# MOD-W_V10.net
KiCad netlist of a schematic drawn in EAGLE
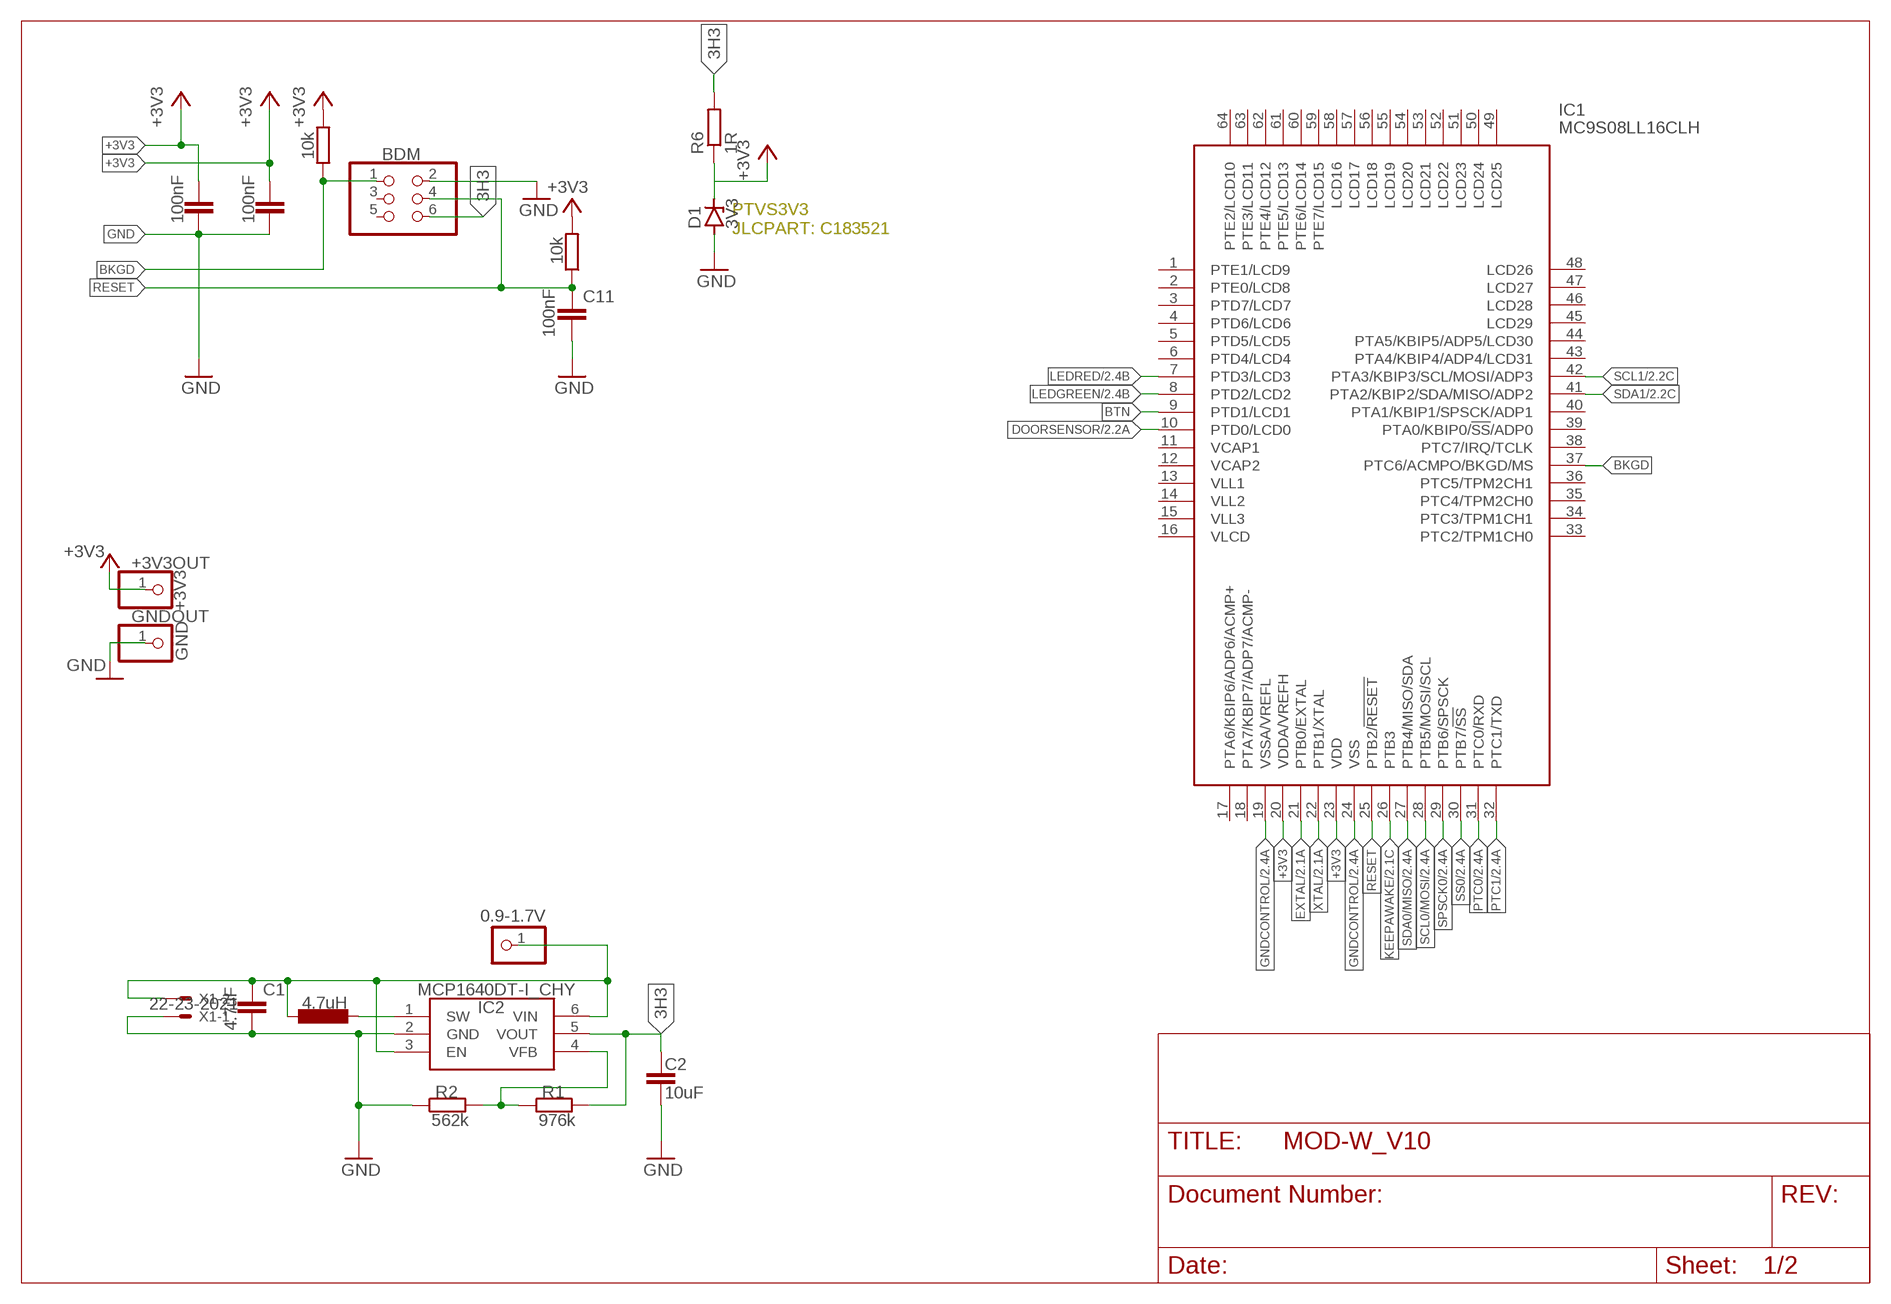
[diagram p0: schematic, sheet 1]
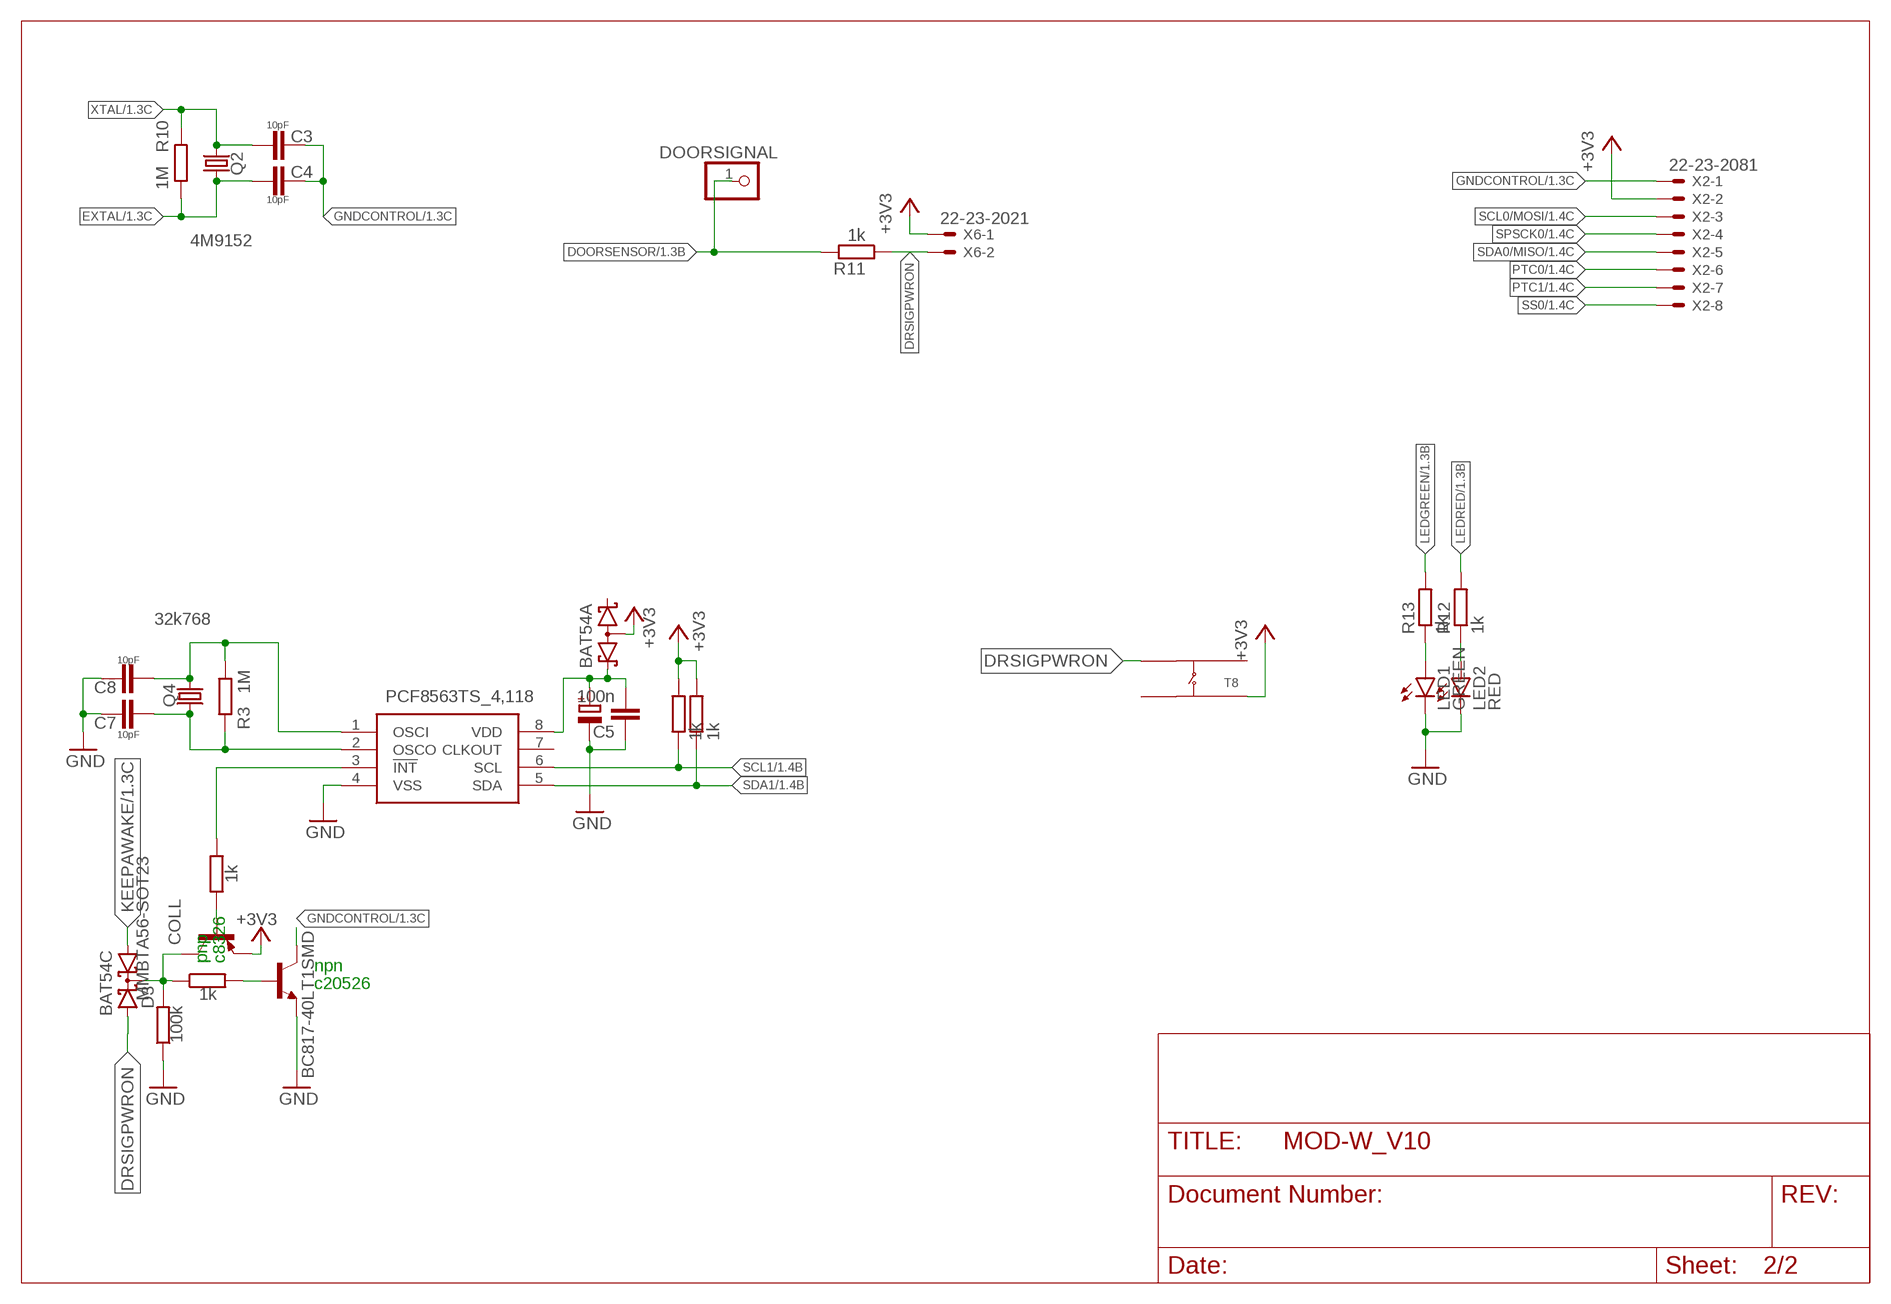
[diagram p1: schematic, sheet 2]

(export (version "E")
  (design (tool "Eeschema 10.0.6"))
  (components
    (comp (ref "C3")
      (value "10pF")
      (footprint "eagle-import:C0805")
      (libsource (lib "eagle-import") (part "C-EUC0805"))
    )
    (comp (ref "C4")
      (value "10pF")
      (footprint "eagle-import:C0805")
      (libsource (lib "eagle-import") (part "C-EUC0805"))
    )
    (comp (ref "C5")
      (value "100n")
      (footprint "eagle-import:C0805")
      (libsource (lib "eagle-import") (part "C-EUC0805"))
    )
    (comp (ref "C6")
      (value "100u")
      (footprint "eagle-import:PANASONIC_E")
      (libsource (lib "eagle-import") (part "CPOL-EUE"))
    )
    (comp (ref "C7")
      (value "10pF")
      (footprint "eagle-import:C0805")
      (libsource (lib "eagle-import") (part "C-EUC0805"))
    )
    (comp (ref "C8")
      (value "10pF")
      (footprint "eagle-import:C0805")
      (libsource (lib "eagle-import") (part "C-EUC0805"))
    )
    (comp (ref "D2")
      (value "BAT54A")
      (footprint "eagle-import:SOT23")
      (libsource (lib "eagle-import") (part "BAT54A"))
    )
    (comp (ref "D3")
      (value "BAT54C")
      (footprint "eagle-import:SOT23")
      (libsource (lib "eagle-import") (part "BAT54C"))
    )
    (comp (ref "DOORSIGNAL")
      (value "PINHD-1X1")
      (footprint "eagle-import:1X01")
      (libsource (lib "eagle-import") (part "PINHD-1X1"))
    )
    (comp (ref "IC3")
      (value "PCF8563TS_4,118")
      (footprint "eagle-import:SOP65P490X110-8N")
      (fields
        (field (name "ARROW_PART_NUMBER") "PCF8563TS/4,118")
        (field (name "MOUSER_PART_NUMBER") "771-PCF8563TS-T")
      )
      (libsource (lib "eagle-import") (part "PCF8563TS_4,118"))
    )
    (comp (ref "LED1")
      (value "GREEN")
      (footprint "eagle-import:CHIP-LED0805")
      (libsource (lib "eagle-import") (part "LEDCHIP-LED0805"))
    )
    (comp (ref "LED2")
      (value "RED")
      (footprint "eagle-import:CHIP-LED0805")
      (libsource (lib "eagle-import") (part "LEDCHIP-LED0805"))
    )
    (comp (ref "Q1")
      (value "MMBTA56-SOT23")
      (footprint "eagle-import:SOT23")
      (libsource (lib "eagle-import") (part "-?SOT23MMBTA56"))
    )
    (comp (ref "Q2")
      (value "4M9152")
      (footprint "eagle-import:HC49UP")
      (libsource (lib "eagle-import") (part "CRYSTALHC49UP"))
    )
    (comp (ref "Q3")
      (value "BC817-40LT1SMD")
      (footprint "eagle-import:SOT23-BEC")
      (libsource (lib "eagle-import") (part "BC817SMD-40LT1"))
    )
    (comp (ref "Q4")
      (value "32k768")
      (footprint "eagle-import:TC38H")
      (libsource (lib "eagle-import") (part "CRYSTALTC38H"))
    )
    (comp (ref "R3")
      (value "1M")
      (footprint "eagle-import:R0805")
      (libsource (lib "eagle-import") (part "R-EU_R0805"))
    )
    (comp (ref "R4")
      (value "1k")
      (footprint "eagle-import:R0805")
      (libsource (lib "eagle-import") (part "R-EU_R0805"))
    )
    (comp (ref "R5")
      (value "1k")
      (footprint "eagle-import:R0805")
      (libsource (lib "eagle-import") (part "R-EU_R0805"))
    )
    (comp (ref "R7")
      (value "1k")
      (footprint "eagle-import:R0805")
      (libsource (lib "eagle-import") (part "R-EU_R0805"))
    )
    (comp (ref "R8")
      (value "1k")
      (footprint "eagle-import:R0805")
      (libsource (lib "eagle-import") (part "R-EU_R0805"))
    )
    (comp (ref "R9")
      (value "100k")
      (footprint "eagle-import:R0805")
      (libsource (lib "eagle-import") (part "R-EU_R0805"))
    )
    (comp (ref "R10")
      (value "1M")
      (footprint "eagle-import:R0805")
      (libsource (lib "eagle-import") (part "R-EU_R0805"))
    )
    (comp (ref "R11")
      (value "1k")
      (footprint "eagle-import:R0805")
      (libsource (lib "eagle-import") (part "R-EU_R0805"))
    )
    (comp (ref "R12")
      (value "1k")
      (footprint "eagle-import:R0805")
      (libsource (lib "eagle-import") (part "R-EU_R0805"))
    )
    (comp (ref "R13")
      (value "1k")
      (footprint "eagle-import:R0805")
      (libsource (lib "eagle-import") (part "R-EU_R0805"))
    )
    (comp (ref "T8")
      (value "TASTERTHT")
      (footprint "eagle-import:TASTE_THT")
      (libsource (lib "eagle-import") (part "TASTERTHT"))
    )
    (comp (ref "X2")
      (value "22-23-2081")
      (footprint "eagle-import:22-23-2081")
      (fields (field (name "MF") "MOLEX"))
      (libsource (lib "eagle-import") (part "22-23-2081"))
    )
    (comp (ref "X6")
      (value "22-23-2021")
      (footprint "eagle-import:22-23-2021")
      (fields (field (name "MF") "MOLEX"))
      (libsource (lib "eagle-import") (part "22-23-2021"))
    )
    (comp (ref "+3V3OUT")
      (value "+3V3")
      (footprint "eagle-import:1X01")
      (libsource (lib "eagle-import") (part "PINHD-1X1"))
    )
    (comp (ref "BAT")
      (value "0.9-1.7V")
      (footprint "eagle-import:1X01")
      (libsource (lib "eagle-import") (part "PINHD-1X1"))
    )
    (comp (ref "BDM")
      (value "PINHD-2X3")
      (footprint "eagle-import:2X03")
      (libsource (lib "eagle-import") (part "PINHD-2X3"))
    )
    (comp (ref "C1")
      (value "4.7uF")
      (footprint "eagle-import:C0805")
      (libsource (lib "eagle-import") (part "C-EUC0805"))
    )
    (comp (ref "C2")
      (value "10uF")
      (footprint "eagle-import:C0805")
      (libsource (lib "eagle-import") (part "C-EUC0805"))
    )
    (comp (ref "C9")
      (value "100nF")
      (footprint "eagle-import:C0805")
      (libsource (lib "eagle-import") (part "C-EUC0805"))
    )
    (comp (ref "C10")
      (value "100nF")
      (footprint "eagle-import:C0805")
      (libsource (lib "eagle-import") (part "C-EUC0805"))
    )
    (comp (ref "C11")
      (value "100nF")
      (footprint "eagle-import:C0805")
      (libsource (lib "eagle-import") (part "C-EUC0805"))
    )
    (comp (ref "D1")
      (value "3V3")
      (footprint "eagle-import:SOD80C")
      (libsource (lib "eagle-import") (part "ZENER-DIODESOD80C"))
    )
    (comp (ref "GNDOUT")
      (value "GND")
      (footprint "eagle-import:1X01")
      (libsource (lib "eagle-import") (part "PINHD-1X1"))
    )
    (comp (ref "IC1")
      (value "MC9S08LL16CLH")
      (footprint "eagle-import:QFP50P1200X1200X160-64N")
      (fields (field (name "MOUSER_PART_NUMBER") "841-MC9S08LL16CLH"))
      (libsource (lib "eagle-import") (part "MC9S08LL16CLH"))
    )
    (comp (ref "IC2")
      (value "MCP1640DT-I_CHY")
      (footprint "eagle-import:SOT95P270X145-6N")
      (fields
        (field (name "ARROW_PART_NUMBER") "MCP1640DT-I/CHY")
        (field (name "MOUSER_PART_NUMBER") "579-MCP1640DT-I/CHY")
      )
      (libsource (lib "eagle-import") (part "MCP1640DT-I_CHY"))
    )
    (comp (ref "L1")
      (value "4.7uH")
      (footprint "eagle-import:L2012C")
      (libsource (lib "eagle-import") (part "L-EUL2012C"))
    )
    (comp (ref "R1")
      (value "976k")
      (footprint "eagle-import:R0805")
      (libsource (lib "eagle-import") (part "R-EU_R0805"))
    )
    (comp (ref "R2")
      (value "562k")
      (footprint "eagle-import:R0805")
      (libsource (lib "eagle-import") (part "R-EU_R0805"))
    )
    (comp (ref "R6")
      (value "1R")
      (footprint "eagle-import:R0805")
      (libsource (lib "eagle-import") (part "R-EU_R0805"))
    )
    (comp (ref "R16")
      (value "10k")
      (footprint "eagle-import:R0805")
      (libsource (lib "eagle-import") (part "R-EU_R0805"))
    )
    (comp (ref "R17")
      (value "10k")
      (footprint "eagle-import:R0805")
      (libsource (lib "eagle-import") (part "R-EU_R0805"))
    )
    (comp (ref "X1")
      (value "22-23-2021")
      (footprint "eagle-import:22-23-2021")
      (fields (field (name "MF") "MOLEX"))
      (libsource (lib "eagle-import") (part "22-23-2021"))
    )
  )
  (nets
    (net (code "1") (name "+3V3") (class "Default")
      (node (ref "+3V3OUT") (pin "1") (pinfunction "1_1") (pintype "passive"))
      (node (ref "C10") (pin "1") (pinfunction "1_1") (pintype "passive"))
      (node (ref "C9") (pin "1") (pinfunction "1_1") (pintype "passive"))
      (node (ref "D1") (pin "C") (pinfunction "C_C") (pintype "passive"))
      (node (ref "D2") (pin "3") (pinfunction "AA_3") (pintype "passive"))
      (node (ref "IC1") (pin "20") (pinfunction "VDDA/VREFH_20") (pintype "bidirectional"))
      (node (ref "IC1") (pin "23") (pinfunction "VDD_23") (pintype "bidirectional"))
      (node (ref "Q1") (pin "2") (pinfunction "E_2") (pintype "passive"))
      (node (ref "R16") (pin "2") (pinfunction "2_2") (pintype "passive"))
      (node (ref "R17") (pin "2") (pinfunction "2_2") (pintype "passive"))
      (node (ref "R4") (pin "2") (pinfunction "2_2") (pintype "passive"))
      (node (ref "R5") (pin "2") (pinfunction "2_2") (pintype "passive"))
      (node (ref "R6") (pin "1") (pinfunction "1_1") (pintype "passive"))
      (node (ref "T8") (pin "A1") (pinfunction "A1_A1") (pintype "bidirectional"))
      (node (ref "X2") (pin "2") (pinfunction "S_2") (pintype "passive"))
      (node (ref "X6") (pin "1") (pinfunction "S_1") (pintype "passive"))
    )
    (net (code "2") (name "3H3") (class "Default")
      (node (ref "BDM") (pin "6") (pinfunction "6_6") (pintype "passive"))
      (node (ref "C2") (pin "1") (pinfunction "1_1") (pintype "passive"))
      (node (ref "IC2") (pin "5") (pinfunction "VOUT_5") (pintype "output"))
      (node (ref "R1") (pin "2") (pinfunction "2_2") (pintype "passive"))
      (node (ref "R6") (pin "2") (pinfunction "2_2") (pintype "passive"))
    )
    (net (code "3") (name "BKGD") (class "Default")
      (node (ref "BDM") (pin "1") (pinfunction "1_1") (pintype "passive"))
      (node (ref "IC1") (pin "37") (pinfunction "PTC6/ACMPO/BKGD/MS_37") (pintype "bidirectional"))
      (node (ref "R16") (pin "1") (pinfunction "1_1") (pintype "passive"))
    )
    (net (code "4") (name "BTN") (class "Default")
      (node (ref "IC1") (pin "9") (pinfunction "PTD1/LCD1_9") (pintype "bidirectional"))
    )
    (net (code "5") (name "COLL") (class "Default")
      (node (ref "D3") (pin "3") (pinfunction "CC_3") (pintype "passive"))
      (node (ref "Q1") (pin "3") (pinfunction "C_3") (pintype "passive"))
      (node (ref "R7") (pin "1") (pinfunction "1_1") (pintype "passive"))
      (node (ref "R9") (pin "2") (pinfunction "2_2") (pintype "passive"))
    )
    (net (code "6") (name "DOORSENSOR") (class "Default")
      (node (ref "DOORSIGNAL") (pin "1") (pinfunction "1_1") (pintype "passive"))
      (node (ref "IC1") (pin "10") (pinfunction "PTD0/LCD0_10") (pintype "bidirectional"))
      (node (ref "R11") (pin "2") (pinfunction "2_2") (pintype "passive"))
    )
    (net (code "7") (name "DRSIGPWRON") (class "Default")
      (node (ref "D3") (pin "2") (pinfunction "A2_2") (pintype "passive"))
      (node (ref "R11") (pin "1") (pinfunction "1_1") (pintype "passive"))
      (node (ref "T8") (pin "B2") (pinfunction "B2_B2") (pintype "bidirectional"))
      (node (ref "X6") (pin "2") (pinfunction "S_2") (pintype "passive"))
    )
    (net (code "8") (name "EXTAL") (class "Default")
      (node (ref "C4") (pin "1") (pinfunction "1_1") (pintype "passive"))
      (node (ref "IC1") (pin "21") (pinfunction "PTB0/EXTAL_21") (pintype "bidirectional"))
      (node (ref "Q2") (pin "1") (pinfunction "1_1") (pintype "passive"))
      (node (ref "R10") (pin "1") (pinfunction "1_1") (pintype "passive"))
    )
    (net (code "9") (name "GND") (class "Default")
      (node (ref "BDM") (pin "2") (pinfunction "2_2") (pintype "passive"))
      (node (ref "C1") (pin "2") (pinfunction "2_2") (pintype "passive"))
      (node (ref "C10") (pin "2") (pinfunction "2_2") (pintype "passive"))
      (node (ref "C11") (pin "2") (pinfunction "2_2") (pintype "passive"))
      (node (ref "C2") (pin "2") (pinfunction "2_2") (pintype "passive"))
      (node (ref "C5") (pin "1") (pinfunction "1_1") (pintype "passive"))
      (node (ref "C6") (pin "-") (pinfunction "-_-") (pintype "passive"))
      (node (ref "C7") (pin "2") (pinfunction "2_2") (pintype "passive"))
      (node (ref "C8") (pin "2") (pinfunction "2_2") (pintype "passive"))
      (node (ref "C9") (pin "2") (pinfunction "2_2") (pintype "passive"))
      (node (ref "D1") (pin "A") (pinfunction "A_A") (pintype "passive"))
      (node (ref "GNDOUT") (pin "1") (pinfunction "1_1") (pintype "passive"))
      (node (ref "IC2") (pin "2") (pinfunction "GND_2") (pintype "power_in"))
      (node (ref "IC3") (pin "4") (pinfunction "VSS_4") (pintype "bidirectional"))
      (node (ref "LED1") (pin "C") (pinfunction "C_C") (pintype "passive"))
      (node (ref "LED2") (pin "C") (pinfunction "C_C") (pintype "passive"))
      (node (ref "Q3") (pin "E") (pinfunction "E_E") (pintype "passive"))
      (node (ref "R2") (pin "1") (pinfunction "1_1") (pintype "passive"))
      (node (ref "R9") (pin "1") (pinfunction "1_1") (pintype "passive"))
      (node (ref "X1") (pin "1") (pinfunction "S_1") (pintype "passive"))
    )
    (net (code "10") (name "GNDCONTROL") (class "Default")
      (node (ref "C3") (pin "2") (pinfunction "2_2") (pintype "passive"))
      (node (ref "C4") (pin "2") (pinfunction "2_2") (pintype "passive"))
      (node (ref "IC1") (pin "19") (pinfunction "VSSA/VREFL_19") (pintype "bidirectional"))
      (node (ref "IC1") (pin "24") (pinfunction "VSS_24") (pintype "bidirectional"))
      (node (ref "Q3") (pin "C") (pinfunction "C_C") (pintype "passive"))
      (node (ref "X2") (pin "1") (pinfunction "S_1") (pintype "passive"))
    )
    (net (code "11") (name "KEEPAWAKE") (class "Default")
      (node (ref "D3") (pin "1") (pinfunction "A1_1") (pintype "passive"))
      (node (ref "IC1") (pin "26") (pinfunction "PTB3_26") (pintype "bidirectional"))
    )
    (net (code "12") (name "LEDGREEN") (class "Default")
      (node (ref "IC1") (pin "8") (pinfunction "PTD2/LCD2_8") (pintype "bidirectional"))
      (node (ref "R13") (pin "2") (pinfunction "2_2") (pintype "passive"))
    )
    (net (code "13") (name "LEDRED") (class "Default")
      (node (ref "IC1") (pin "7") (pinfunction "PTD3/LCD3_7") (pintype "bidirectional"))
      (node (ref "R12") (pin "2") (pinfunction "2_2") (pintype "passive"))
    )
    (net (code "14") (name "Net-(D2-K2)") (class "Default")
      (node (ref "C5") (pin "2") (pinfunction "2_2") (pintype "passive"))
      (node (ref "C6") (pin "+") (pinfunction "+_+") (pintype "passive"))
      (node (ref "D2") (pin "2") (pinfunction "K2_2") (pintype "passive"))
      (node (ref "IC3") (pin "8") (pinfunction "VDD_8") (pintype "bidirectional"))
    )
    (net (code "15") (name "Net-(IC2-EN)") (class "Default")
      (node (ref "BAT") (pin "1") (pinfunction "1_1") (pintype "passive"))
      (node (ref "C1") (pin "1") (pinfunction "1_1") (pintype "passive"))
      (node (ref "IC2") (pin "3") (pinfunction "EN_3") (pintype "power_in"))
      (node (ref "IC2") (pin "6") (pinfunction "VIN_6") (pintype "input"))
      (node (ref "L1") (pin "2") (pinfunction "2_2") (pintype "passive"))
      (node (ref "X1") (pin "2") (pinfunction "S_2") (pintype "passive"))
    )
    (net (code "16") (name "Net-(IC2-SW)") (class "Default")
      (node (ref "IC2") (pin "1") (pinfunction "SW_1") (pintype "input"))
      (node (ref "L1") (pin "1") (pinfunction "1_1") (pintype "passive"))
    )
    (net (code "17") (name "Net-(IC2-VFB)") (class "Default")
      (node (ref "IC2") (pin "4") (pinfunction "VFB_4") (pintype "bidirectional"))
      (node (ref "R1") (pin "1") (pinfunction "1_1") (pintype "passive"))
      (node (ref "R2") (pin "2") (pinfunction "2_2") (pintype "passive"))
    )
    (net (code "18") (name "Net-(IC3-OSCI)") (class "Default")
      (node (ref "C8") (pin "1") (pinfunction "1_1") (pintype "passive"))
      (node (ref "IC3") (pin "1") (pinfunction "OSCI_1") (pintype "bidirectional"))
      (node (ref "Q4") (pin "1") (pinfunction "1_1") (pintype "passive"))
      (node (ref "R3") (pin "1") (pinfunction "1_1") (pintype "passive"))
    )
    (net (code "19") (name "Net-(IC3-OSCO)") (class "Default")
      (node (ref "C7") (pin "1") (pinfunction "1_1") (pintype "passive"))
      (node (ref "IC3") (pin "2") (pinfunction "OSCO_2") (pintype "bidirectional"))
      (node (ref "Q4") (pin "2") (pinfunction "2_2") (pintype "passive"))
      (node (ref "R3") (pin "2") (pinfunction "2_2") (pintype "passive"))
    )
    (net (code "20") (name "Net-(IC3-~{INT})") (class "Default")
      (node (ref "IC3") (pin "3") (pinfunction "~{INT}_3") (pintype "bidirectional"))
      (node (ref "R8") (pin "2") (pinfunction "2_2") (pintype "passive"))
    )
    (net (code "21") (name "Net-(LED1-PadA)") (class "Default")
      (node (ref "LED1") (pin "A") (pinfunction "A_A") (pintype "passive"))
      (node (ref "R13") (pin "1") (pinfunction "1_1") (pintype "passive"))
    )
    (net (code "22") (name "Net-(LED2-PadA)") (class "Default")
      (node (ref "LED2") (pin "A") (pinfunction "A_A") (pintype "passive"))
      (node (ref "R12") (pin "1") (pinfunction "1_1") (pintype "passive"))
    )
    (net (code "23") (name "Net-(Q1-B)") (class "Default")
      (node (ref "Q1") (pin "1") (pinfunction "B_1") (pintype "passive"))
      (node (ref "R8") (pin "1") (pinfunction "1_1") (pintype "passive"))
    )
    (net (code "24") (name "Net-(Q3-PadB)") (class "Default")
      (node (ref "Q3") (pin "B") (pinfunction "B_B") (pintype "passive"))
      (node (ref "R7") (pin "2") (pinfunction "2_2") (pintype "passive"))
    )
    (net (code "25") (name "PTC0") (class "Default")
      (node (ref "IC1") (pin "31") (pinfunction "PTC0/RXD_31") (pintype "bidirectional"))
      (node (ref "X2") (pin "6") (pinfunction "S_6") (pintype "passive"))
    )
    (net (code "26") (name "PTC1") (class "Default")
      (node (ref "IC1") (pin "32") (pinfunction "PTC1/TXD_32") (pintype "bidirectional"))
      (node (ref "X2") (pin "7") (pinfunction "S_7") (pintype "passive"))
    )
    (net (code "27") (name "RESET") (class "Default")
      (node (ref "BDM") (pin "4") (pinfunction "4_4") (pintype "passive"))
      (node (ref "C11") (pin "1") (pinfunction "1_1") (pintype "passive"))
      (node (ref "IC1") (pin "25") (pinfunction "PTB2/~{RESET}_25") (pintype "bidirectional"))
      (node (ref "R17") (pin "1") (pinfunction "1_1") (pintype "passive"))
    )
    (net (code "28") (name "SCL0{slash}MOSI") (class "Default")
      (node (ref "IC1") (pin "28") (pinfunction "PTB5/MOSI/SCL_28") (pintype "bidirectional"))
      (node (ref "X2") (pin "3") (pinfunction "S_3") (pintype "passive"))
    )
    (net (code "29") (name "SCL1") (class "Default")
      (node (ref "IC1") (pin "42") (pinfunction "PTA3/KBIP3/SCL/MOSI/ADP3_42") (pintype "bidirectional"))
      (node (ref "IC3") (pin "6") (pinfunction "SCL_6") (pintype "bidirectional"))
      (node (ref "R4") (pin "1") (pinfunction "1_1") (pintype "passive"))
    )
    (net (code "30") (name "SDA0{slash}MISO") (class "Default")
      (node (ref "IC1") (pin "27") (pinfunction "PTB4/MISO/SDA_27") (pintype "bidirectional"))
      (node (ref "X2") (pin "5") (pinfunction "S_5") (pintype "passive"))
    )
    (net (code "31") (name "SDA1") (class "Default")
      (node (ref "IC1") (pin "41") (pinfunction "PTA2/KBIP2/SDA/MISO/ADP2_41") (pintype "bidirectional"))
      (node (ref "IC3") (pin "5") (pinfunction "SDA_5") (pintype "bidirectional"))
      (node (ref "R5") (pin "1") (pinfunction "1_1") (pintype "passive"))
    )
    (net (code "32") (name "SPSCK0") (class "Default")
      (node (ref "IC1") (pin "29") (pinfunction "PTB6/SPSCK_29") (pintype "bidirectional"))
      (node (ref "X2") (pin "4") (pinfunction "S_4") (pintype "passive"))
    )
    (net (code "33") (name "SS0") (class "Default")
      (node (ref "IC1") (pin "30") (pinfunction "PTB7/~{SS}_30") (pintype "bidirectional"))
      (node (ref "X2") (pin "8") (pinfunction "S_8") (pintype "passive"))
    )
    (net (code "34") (name "XTAL") (class "Default")
      (node (ref "C3") (pin "1") (pinfunction "1_1") (pintype "passive"))
      (node (ref "IC1") (pin "22") (pinfunction "PTB1/XTAL_22") (pintype "bidirectional"))
      (node (ref "Q2") (pin "2") (pinfunction "2_2") (pintype "passive"))
      (node (ref "R10") (pin "2") (pinfunction "2_2") (pintype "passive"))
    )
    (net (code "35") (name "unconnected-(BDM-Pad3)") (class "Default")
      (node (ref "BDM") (pin "3") (pinfunction "3_3") (pintype "passive"))
    )
    (net (code "36") (name "unconnected-(BDM-Pad5)") (class "Default")
      (node (ref "BDM") (pin "5") (pinfunction "5_5") (pintype "passive"))
    )
    (net (code "37") (name "unconnected-(D2-K1-Pad1)") (class "Default")
      (node (ref "D2") (pin "1") (pinfunction "K1_1") (pintype "passive"))
    )
    (net (code "38") (name "unconnected-(IC1-LCD16-Pad58)") (class "Default")
      (node (ref "IC1") (pin "58") (pinfunction "LCD16_58") (pintype "bidirectional"))
    )
    (net (code "39") (name "unconnected-(IC1-LCD17-Pad57)") (class "Default")
      (node (ref "IC1") (pin "57") (pinfunction "LCD17_57") (pintype "bidirectional"))
    )
    (net (code "40") (name "unconnected-(IC1-LCD18-Pad56)") (class "Default")
      (node (ref "IC1") (pin "56") (pinfunction "LCD18_56") (pintype "bidirectional"))
    )
    (net (code "41") (name "unconnected-(IC1-LCD19-Pad55)") (class "Default")
      (node (ref "IC1") (pin "55") (pinfunction "LCD19_55") (pintype "bidirectional"))
    )
    (net (code "42") (name "unconnected-(IC1-LCD20-Pad54)") (class "Default")
      (node (ref "IC1") (pin "54") (pinfunction "LCD20_54") (pintype "bidirectional"))
    )
    (net (code "43") (name "unconnected-(IC1-LCD21-Pad53)") (class "Default")
      (node (ref "IC1") (pin "53") (pinfunction "LCD21_53") (pintype "bidirectional"))
    )
    (net (code "44") (name "unconnected-(IC1-LCD22-Pad52)") (class "Default")
      (node (ref "IC1") (pin "52") (pinfunction "LCD22_52") (pintype "bidirectional"))
    )
    (net (code "45") (name "unconnected-(IC1-LCD23-Pad51)") (class "Default")
      (node (ref "IC1") (pin "51") (pinfunction "LCD23_51") (pintype "bidirectional"))
    )
    (net (code "46") (name "unconnected-(IC1-LCD24-Pad50)") (class "Default")
      (node (ref "IC1") (pin "50") (pinfunction "LCD24_50") (pintype "bidirectional"))
    )
    (net (code "47") (name "unconnected-(IC1-LCD25-Pad49)") (class "Default")
      (node (ref "IC1") (pin "49") (pinfunction "LCD25_49") (pintype "bidirectional"))
    )
    (net (code "48") (name "unconnected-(IC1-LCD26-Pad48)") (class "Default")
      (node (ref "IC1") (pin "48") (pinfunction "LCD26_48") (pintype "bidirectional"))
    )
    (net (code "49") (name "unconnected-(IC1-LCD27-Pad47)") (class "Default")
      (node (ref "IC1") (pin "47") (pinfunction "LCD27_47") (pintype "bidirectional"))
    )
    (net (code "50") (name "unconnected-(IC1-LCD28-Pad46)") (class "Default")
      (node (ref "IC1") (pin "46") (pinfunction "LCD28_46") (pintype "bidirectional"))
    )
    (net (code "51") (name "unconnected-(IC1-LCD29-Pad45)") (class "Default")
      (node (ref "IC1") (pin "45") (pinfunction "LCD29_45") (pintype "bidirectional"))
    )
    (net (code "52") (name "unconnected-(IC1-PTA0{slash}KBIP0{slash}~{SS}{slash}ADP0-Pad39)") (class "Default")
      (node (ref "IC1") (pin "39") (pinfunction "PTA0/KBIP0/~{SS}/ADP0_39") (pintype "bidirectional"))
    )
    (net (code "53") (name "unconnected-(IC1-PTA1{slash}KBIP1{slash}SPSCK{slash}ADP1-Pad40)") (class "Default")
      (node (ref "IC1") (pin "40") (pinfunction "PTA1/KBIP1/SPSCK/ADP1_40") (pintype "bidirectional"))
    )
    (net (code "54") (name "unconnected-(IC1-PTA4{slash}KBIP4{slash}ADP4{slash}LCD31-Pad43)") (class "Default")
      (node (ref "IC1") (pin "43") (pinfunction "PTA4/KBIP4/ADP4/LCD31_43") (pintype "bidirectional"))
    )
    (net (code "55") (name "unconnected-(IC1-PTA5{slash}KBIP5{slash}ADP5{slash}LCD30-Pad44)") (class "Default")
      (node (ref "IC1") (pin "44") (pinfunction "PTA5/KBIP5/ADP5/LCD30_44") (pintype "bidirectional"))
    )
    (net (code "56") (name "unconnected-(IC1-PTA6{slash}KBIP6{slash}ADP6{slash}ACMP+-Pad17)") (class "Default")
      (node (ref "IC1") (pin "17") (pinfunction "PTA6/KBIP6/ADP6/ACMP+_17") (pintype "bidirectional"))
    )
    (net (code "57") (name "unconnected-(IC1-PTA7{slash}KBIP7{slash}ADP7{slash}ACMP--Pad18)") (class "Default")
      (node (ref "IC1") (pin "18") (pinfunction "PTA7/KBIP7/ADP7/ACMP-_18") (pintype "bidirectional"))
    )
    (net (code "58") (name "unconnected-(IC1-PTC2{slash}TPM1CH0-Pad33)") (class "Default")
      (node (ref "IC1") (pin "33") (pinfunction "PTC2/TPM1CH0_33") (pintype "bidirectional"))
    )
    (net (code "59") (name "unconnected-(IC1-PTC3{slash}TPM1CH1-Pad34)") (class "Default")
      (node (ref "IC1") (pin "34") (pinfunction "PTC3/TPM1CH1_34") (pintype "bidirectional"))
    )
    (net (code "60") (name "unconnected-(IC1-PTC4{slash}TPM2CH0-Pad35)") (class "Default")
      (node (ref "IC1") (pin "35") (pinfunction "PTC4/TPM2CH0_35") (pintype "bidirectional"))
    )
    (net (code "61") (name "unconnected-(IC1-PTC5{slash}TPM2CH1-Pad36)") (class "Default")
      (node (ref "IC1") (pin "36") (pinfunction "PTC5/TPM2CH1_36") (pintype "bidirectional"))
    )
    (net (code "62") (name "unconnected-(IC1-PTC7{slash}IRQ{slash}TCLK-Pad38)") (class "Default")
      (node (ref "IC1") (pin "38") (pinfunction "PTC7/IRQ/TCLK_38") (pintype "bidirectional"))
    )
    (net (code "63") (name "unconnected-(IC1-PTD4{slash}LCD4-Pad6)") (class "Default")
      (node (ref "IC1") (pin "6") (pinfunction "PTD4/LCD4_6") (pintype "bidirectional"))
    )
    (net (code "64") (name "unconnected-(IC1-PTD5{slash}LCD5-Pad5)") (class "Default")
      (node (ref "IC1") (pin "5") (pinfunction "PTD5/LCD5_5") (pintype "bidirectional"))
    )
    (net (code "65") (name "unconnected-(IC1-PTD6{slash}LCD6-Pad4)") (class "Default")
      (node (ref "IC1") (pin "4") (pinfunction "PTD6/LCD6_4") (pintype "bidirectional"))
    )
    (net (code "66") (name "unconnected-(IC1-PTD7{slash}LCD7-Pad3)") (class "Default")
      (node (ref "IC1") (pin "3") (pinfunction "PTD7/LCD7_3") (pintype "bidirectional"))
    )
    (net (code "67") (name "unconnected-(IC1-PTE0{slash}LCD8-Pad2)") (class "Default")
      (node (ref "IC1") (pin "2") (pinfunction "PTE0/LCD8_2") (pintype "bidirectional"))
    )
    (net (code "68") (name "unconnected-(IC1-PTE1{slash}LCD9-Pad1)") (class "Default")
      (node (ref "IC1") (pin "1") (pinfunction "PTE1/LCD9_1") (pintype "bidirectional"))
    )
    (net (code "69") (name "unconnected-(IC1-PTE2{slash}LCD10-Pad64)") (class "Default")
      (node (ref "IC1") (pin "64") (pinfunction "PTE2/LCD10_64") (pintype "bidirectional"))
    )
    (net (code "70") (name "unconnected-(IC1-PTE3{slash}LCD11-Pad63)") (class "Default")
      (node (ref "IC1") (pin "63") (pinfunction "PTE3/LCD11_63") (pintype "bidirectional"))
    )
    (net (code "71") (name "unconnected-(IC1-PTE4{slash}LCD12-Pad62)") (class "Default")
      (node (ref "IC1") (pin "62") (pinfunction "PTE4/LCD12_62") (pintype "bidirectional"))
    )
    (net (code "72") (name "unconnected-(IC1-PTE5{slash}LCD13-Pad61)") (class "Default")
      (node (ref "IC1") (pin "61") (pinfunction "PTE5/LCD13_61") (pintype "bidirectional"))
    )
    (net (code "73") (name "unconnected-(IC1-PTE6{slash}LCD14-Pad60)") (class "Default")
      (node (ref "IC1") (pin "60") (pinfunction "PTE6/LCD14_60") (pintype "bidirectional"))
    )
    (net (code "74") (name "unconnected-(IC1-PTE7{slash}LCD15-Pad59)") (class "Default")
      (node (ref "IC1") (pin "59") (pinfunction "PTE7/LCD15_59") (pintype "bidirectional"))
    )
    (net (code "75") (name "unconnected-(IC1-VCAP1-Pad11)") (class "Default")
      (node (ref "IC1") (pin "11") (pinfunction "VCAP1_11") (pintype "bidirectional"))
    )
    (net (code "76") (name "unconnected-(IC1-VCAP2-Pad12)") (class "Default")
      (node (ref "IC1") (pin "12") (pinfunction "VCAP2_12") (pintype "bidirectional"))
    )
    (net (code "77") (name "unconnected-(IC1-VLCD-Pad16)") (class "Default")
      (node (ref "IC1") (pin "16") (pinfunction "VLCD_16") (pintype "bidirectional"))
    )
    (net (code "78") (name "unconnected-(IC1-VLL1-Pad13)") (class "Default")
      (node (ref "IC1") (pin "13") (pinfunction "VLL1_13") (pintype "bidirectional"))
    )
    (net (code "79") (name "unconnected-(IC1-VLL2-Pad14)") (class "Default")
      (node (ref "IC1") (pin "14") (pinfunction "VLL2_14") (pintype "bidirectional"))
    )
    (net (code "80") (name "unconnected-(IC1-VLL3-Pad15)") (class "Default")
      (node (ref "IC1") (pin "15") (pinfunction "VLL3_15") (pintype "bidirectional"))
    )
    (net (code "81") (name "unconnected-(IC3-CLKOUT-Pad7)") (class "Default")
      (node (ref "IC3") (pin "7") (pinfunction "CLKOUT_7") (pintype "bidirectional"))
    )
    (net (code "82") (name "unconnected-(T8-PadA2)") (class "Default")
      (node (ref "T8") (pin "A2") (pinfunction "A2_A2") (pintype "bidirectional"))
    )
    (net (code "83") (name "unconnected-(T8-PadB1)") (class "Default")
      (node (ref "T8") (pin "B1") (pinfunction "B1_B1") (pintype "bidirectional"))
    )
  )
)
